# TH_Board.net
KiCad netlist of a schematic drawn in Altium Designer
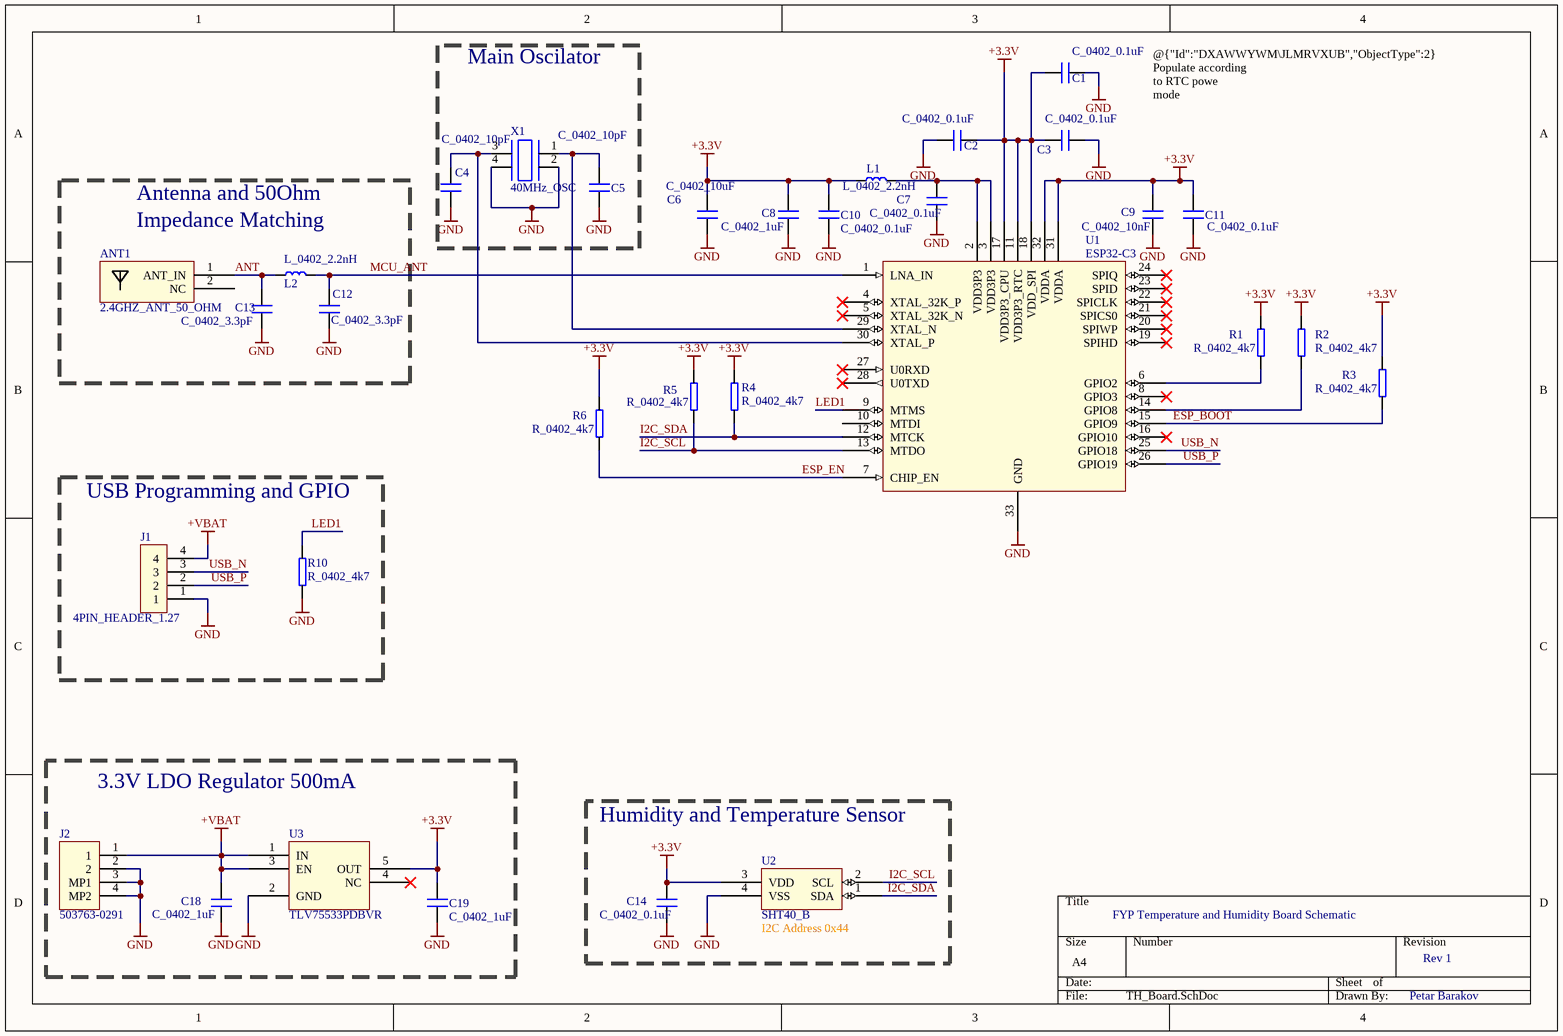
[diagram p0: TH_Board.SchDoc]

(export (version "E")
  (design (tool "Eeschema 10.0.6"))
  (components
    (comp (ref "ANT1")
      (value "2.4GHZ_ANT_50_OHM")
      (footprint "Chip2PinSM127P600-8N")
      (description "2.4GHz Chip Antenna 50 Ohm Impedance ANT2012LL00R2400A")
      (libsource (lib "Petar B") (part "2.4GHZ_ANT_50_OHM"))
    )
    (comp (ref "C1")
      (value "C_0402_0.1uF")
      (footprint "C_0402")
      (fields (field (name "JLC PART NUMBER") "C1525"))
      (libsource (lib "Petar B") (part "Cap_symbol"))
    )
    (comp (ref "C2")
      (value "C_0402_0.1uF")
      (footprint "C_0402")
      (fields (field (name "JLC PART NUMBER") "C1525"))
      (libsource (lib "Petar B") (part "Cap_symbol"))
    )
    (comp (ref "C3")
      (value "C_0402_0.1uF")
      (footprint "C_0402")
      (fields (field (name "JLC PART NUMBER") "C1525"))
      (libsource (lib "Petar B") (part "Cap_symbol"))
    )
    (comp (ref "C4")
      (value "C_0402_10pF")
      (footprint "C_0402")
      (fields (field (name "JLC PART NUMBER") "C32949"))
      (libsource (lib "Petar B") (part "Cap_symbol"))
    )
    (comp (ref "C5")
      (value "C_0402_10pF")
      (footprint "C_0402")
      (fields (field (name "JLC PART NUMBER") "C32949"))
      (libsource (lib "Petar B") (part "Cap_symbol"))
    )
    (comp (ref "C6")
      (value "C_0402_10uF")
      (footprint "C_0402")
      (fields (field (name "JLC PART NUMBER") "C15525"))
      (libsource (lib "Petar B") (part "Cap_symbol"))
    )
    (comp (ref "C7")
      (value "C_0402_0.1uF")
      (footprint "C_0402")
      (fields (field (name "JLC PART NUMBER") "C1525"))
      (libsource (lib "Petar B") (part "Cap_symbol"))
    )
    (comp (ref "C8")
      (value "C_0402_1uF")
      (footprint "C_0402")
      (fields (field (name "JLC PART NUMBER") "C52923"))
      (libsource (lib "Petar B") (part "Cap_symbol"))
    )
    (comp (ref "C9")
      (value "C_0402_10nF")
      (footprint "C_0402")
      (fields (field (name "JLC PART NUMBER") "C15195"))
      (libsource (lib "Petar B") (part "Cap_symbol"))
    )
    (comp (ref "C10")
      (value "C_0402_0.1uF")
      (footprint "C_0402")
      (fields (field (name "JLC PART NUMBER") "C1525"))
      (libsource (lib "Petar B") (part "Cap_symbol"))
    )
    (comp (ref "C11")
      (value "C_0402_0.1uF")
      (footprint "C_0402")
      (fields (field (name "JLC PART NUMBER") "C1525"))
      (libsource (lib "Petar B") (part "Cap_symbol"))
    )
    (comp (ref "C12")
      (value "C_0402_3.3pF")
      (footprint "C_0402")
      (fields (field (name "JLC PART NUMBER") "C326841"))
      (libsource (lib "Petar B") (part "Cap_symbol"))
    )
    (comp (ref "C13")
      (value "C_0402_3.3pF")
      (footprint "C_0402")
      (fields (field (name "JLC PART NUMBER") "C326841"))
      (libsource (lib "Petar B") (part "Cap_symbol"))
    )
    (comp (ref "C14")
      (value "C_0402_0.1uF")
      (footprint "C_0402")
      (fields (field (name "JLC PART NUMBER") "C1525"))
      (libsource (lib "Petar B") (part "Cap_symbol"))
    )
    (comp (ref "C18")
      (value "C_0402_1uF")
      (footprint "C_0402")
      (fields (field (name "JLC PART NUMBER") "C52923"))
      (libsource (lib "Petar B") (part "Cap_symbol"))
    )
    (comp (ref "C19")
      (value "C_0402_1uF")
      (footprint "C_0402")
      (fields (field (name "JLC PART NUMBER") "C52923"))
      (libsource (lib "Petar B") (part "Cap_symbol"))
    )
    (comp (ref "J1")
      (value "4PIN_HEADER_1.27")
      (footprint "4PIN_HEADER_1.27-Footprint-1")
      (libsource (lib "Petar B") (part "4PIN_HEADER_1.27-Symbol-1"))
    )
    (comp (ref "J2")
      (value "503763-0291")
      (footprint "Molex 503763-0291")
      (description "Molex 503763-0291")
      (libsource (lib "Petar B") (part "503763-0291"))
    )
    (comp (ref "L1")
      (value "L_0402_2.2nH")
      (footprint "L_0402")
      (fields (field (name "JLC PART NUMBER") "C92035"))
      (libsource (lib "Petar B") (part "Ind_Symbol"))
    )
    (comp (ref "L2")
      (value "L_0402_2.2nH")
      (footprint "L_0402")
      (fields (field (name "JLC PART NUMBER") "C92035"))
      (libsource (lib "Petar B") (part "Ind_Symbol"))
    )
    (comp (ref "R1")
      (value "R_0402_4k7")
      (footprint "R_0402")
      (fields (field (name "JLC PART NUMBER") "C25900"))
      (libsource (lib "Petar B") (part "R_symbol"))
    )
    (comp (ref "R2")
      (value "R_0402_4k7")
      (footprint "R_0402")
      (fields (field (name "JLC PART NUMBER") "C25900"))
      (libsource (lib "Petar B") (part "R_symbol"))
    )
    (comp (ref "R3")
      (value "R_0402_4k7")
      (footprint "R_0402")
      (fields (field (name "JLC PART NUMBER") "C25900"))
      (libsource (lib "Petar B") (part "R_symbol"))
    )
    (comp (ref "R4")
      (value "R_0402_4k7")
      (footprint "R_0402")
      (fields (field (name "JLC PART NUMBER") "C25900"))
      (libsource (lib "Petar B") (part "R_symbol"))
    )
    (comp (ref "R5")
      (value "R_0402_4k7")
      (footprint "R_0402")
      (fields (field (name "JLC PART NUMBER") "C25900"))
      (libsource (lib "Petar B") (part "R_symbol"))
    )
    (comp (ref "R6")
      (value "R_0402_4k7")
      (footprint "R_0402")
      (fields (field (name "JLC PART NUMBER") "C25900"))
      (libsource (lib "Petar B") (part "R_symbol"))
    )
    (comp (ref "R10")
      (value "R_0402_4k7")
      (footprint "R_0402")
      (fields (field (name "JLC PART NUMBER") "C25900"))
      (libsource (lib "Petar B") (part "R_symbol"))
    )
    (comp (ref "U1")
      (value "ESP32-C3")
      (footprint "QFN127P600-8N")
      (description "33 pin ESP32_C3 Microcontroller")
      (fields (field (name "JLC PART NUMBER") "C2858491"))
      (libsource (lib "Petar B") (part "ESP32-C3_symbol"))
    )
    (comp (ref "U2")
      (value "SHT40_B")
      (footprint "SHT40_B-Footprint-1")
      (fields (field (name "JLC PART NUMBER") "C3664342"))
      (libsource (lib "Petar B") (part "SHT40"))
    )
    (comp (ref "U3")
      (value "TLV75533PDBVR")
      (footprint "SOT95P280X145-5N")
      (fields (field (name "JLC PART NUMBER") "C404027"))
      (libsource (lib "Petar B") (part "TLV75533PDBVR-Symbol"))
    )
    (comp (ref "X1")
      (value "40MHz_OSC")
      (footprint "40MHz_OSC-Footprint-1")
      (description "40 MHZ Oscillator, 10pF load capacitance")
      (fields (field (name "JLC PART NUMBER") "C426988"))
      (libsource (lib "Petar B") (part "OSC_SYMB"))
    )
  )
  (nets
    (net (code "1") (name "+3.3V") (class "Default")
      (node (ref "C1") (pin "1") (pinfunction "1_1") (pintype "passive"))
      (node (ref "C10") (pin "1") (pinfunction "1_1") (pintype "passive"))
      (node (ref "C11") (pin "2") (pinfunction "2_2") (pintype "passive"))
      (node (ref "C14") (pin "1") (pinfunction "1_1") (pintype "passive"))
      (node (ref "C19") (pin "2") (pinfunction "2_2") (pintype "passive"))
      (node (ref "C2") (pin "2") (pinfunction "2_2") (pintype "passive"))
      (node (ref "C3") (pin "1") (pinfunction "1_1") (pintype "passive"))
      (node (ref "C6") (pin "2") (pinfunction "2_2") (pintype "passive"))
      (node (ref "C8") (pin "2") (pinfunction "2_2") (pintype "passive"))
      (node (ref "C9") (pin "2") (pinfunction "2_2") (pintype "passive"))
      (node (ref "L1") (pin "1") (pinfunction "1_1") (pintype "passive"))
      (node (ref "R1") (pin "1") (pinfunction "1_1") (pintype "passive"))
      (node (ref "R2") (pin "1") (pinfunction "1_1") (pintype "passive"))
      (node (ref "R3") (pin "1") (pinfunction "1_1") (pintype "passive"))
      (node (ref "R4") (pin "1") (pinfunction "1_1") (pintype "passive"))
      (node (ref "R5") (pin "1") (pinfunction "1_1") (pintype "passive"))
      (node (ref "R6") (pin "1") (pinfunction "1_1") (pintype "passive"))
      (node (ref "U1") (pin "11") (pinfunction "VDD3P3_RTC_11") (pintype "power_in"))
      (node (ref "U1") (pin "17") (pinfunction "VDD3P3_CPU_17") (pintype "power_in"))
      (node (ref "U1") (pin "18") (pinfunction "VDD_SPI_18") (pintype "power_in"))
      (node (ref "U1") (pin "31") (pinfunction "VDDA_31") (pintype "power_in"))
      (node (ref "U1") (pin "32") (pinfunction "VDDA_32") (pintype "power_in"))
      (node (ref "U2") (pin "3") (pinfunction "VDD_3") (pintype "power_in"))
      (node (ref "U3") (pin "5") (pinfunction "OUT_5") (pintype "passive"))
    )
    (net (code "2") (name "+VBAT") (class "Default")
      (node (ref "C18") (pin "2") (pinfunction "2_2") (pintype "passive"))
      (node (ref "J1") (pin "4") (pinfunction "4_4") (pintype "passive"))
      (node (ref "J2") (pin "1") (pinfunction "1_1") (pintype "passive"))
      (node (ref "U3") (pin "1") (pinfunction "IN_1") (pintype "passive"))
      (node (ref "U3") (pin "3") (pinfunction "EN_3") (pintype "passive"))
    )
    (net (code "3") (name "/ANT") (class "Default")
      (node (ref "ANT1") (pin "1") (pinfunction "ANT_IN_1") (pintype "passive"))
      (node (ref "C13") (pin "2") (pinfunction "2_2") (pintype "passive"))
      (node (ref "L2") (pin "1") (pinfunction "1_1") (pintype "passive"))
    )
    (net (code "4") (name "/ESP_BOOT") (class "Default")
      (node (ref "R3") (pin "2") (pinfunction "2_2") (pintype "passive"))
      (node (ref "U1") (pin "15") (pinfunction "GPIO9_15") (pintype "bidirectional"))
    )
    (net (code "5") (name "/ESP_EN") (class "Default")
      (node (ref "R6") (pin "2") (pinfunction "2_2") (pintype "passive"))
      (node (ref "U1") (pin "7") (pinfunction "CHIP_EN_7") (pintype "input"))
    )
    (net (code "6") (name "/I2C_SCL") (class "Default")
      (node (ref "R5") (pin "2") (pinfunction "2_2") (pintype "passive"))
      (node (ref "U1") (pin "13") (pinfunction "MTDO_13") (pintype "bidirectional"))
      (node (ref "U2") (pin "2") (pinfunction "SCL_2") (pintype "bidirectional"))
    )
    (net (code "7") (name "/I2C_SDA") (class "Default")
      (node (ref "R4") (pin "2") (pinfunction "2_2") (pintype "passive"))
      (node (ref "U1") (pin "12") (pinfunction "MTCK_12") (pintype "bidirectional"))
      (node (ref "U2") (pin "1") (pinfunction "SDA_1") (pintype "bidirectional"))
    )
    (net (code "8") (name "/LED1") (class "Default")
      (node (ref "R10") (pin "1") (pinfunction "1_1") (pintype "passive"))
      (node (ref "U1") (pin "9") (pinfunction "MTMS_9") (pintype "bidirectional"))
    )
    (net (code "9") (name "/MCU_ANT") (class "Default")
      (node (ref "C12") (pin "2") (pinfunction "2_2") (pintype "passive"))
      (node (ref "L2") (pin "2") (pinfunction "2_2") (pintype "passive"))
      (node (ref "U1") (pin "1") (pinfunction "LNA_IN_1") (pintype "input"))
    )
    (net (code "10") (name "/USB_N") (class "Default")
      (node (ref "J1") (pin "3") (pinfunction "3_3") (pintype "passive"))
      (node (ref "U1") (pin "25") (pinfunction "GPIO18_25") (pintype "bidirectional"))
    )
    (net (code "11") (name "/USB_P") (class "Default")
      (node (ref "J1") (pin "2") (pinfunction "2_2") (pintype "passive"))
      (node (ref "U1") (pin "26") (pinfunction "GPIO19_26") (pintype "bidirectional"))
    )
    (net (code "12") (name "GND") (class "Default")
      (node (ref "C1") (pin "2") (pinfunction "2_2") (pintype "passive"))
      (node (ref "C10") (pin "2") (pinfunction "2_2") (pintype "passive"))
      (node (ref "C11") (pin "1") (pinfunction "1_1") (pintype "passive"))
      (node (ref "C12") (pin "1") (pinfunction "1_1") (pintype "passive"))
      (node (ref "C13") (pin "1") (pinfunction "1_1") (pintype "passive"))
      (node (ref "C14") (pin "2") (pinfunction "2_2") (pintype "passive"))
      (node (ref "C18") (pin "1") (pinfunction "1_1") (pintype "passive"))
      (node (ref "C19") (pin "1") (pinfunction "1_1") (pintype "passive"))
      (node (ref "C2") (pin "1") (pinfunction "1_1") (pintype "passive"))
      (node (ref "C3") (pin "2") (pinfunction "2_2") (pintype "passive"))
      (node (ref "C4") (pin "1") (pinfunction "1_1") (pintype "passive"))
      (node (ref "C5") (pin "1") (pinfunction "1_1") (pintype "passive"))
      (node (ref "C6") (pin "1") (pinfunction "1_1") (pintype "passive"))
      (node (ref "C7") (pin "2") (pinfunction "2_2") (pintype "passive"))
      (node (ref "C8") (pin "1") (pinfunction "1_1") (pintype "passive"))
      (node (ref "C9") (pin "1") (pinfunction "1_1") (pintype "passive"))
      (node (ref "J1") (pin "1") (pinfunction "1_1") (pintype "passive"))
      (node (ref "J2") (pin "2") (pinfunction "2_2") (pintype "passive"))
      (node (ref "J2") (pin "3") (pinfunction "MP1_3") (pintype "passive"))
      (node (ref "J2") (pin "4") (pinfunction "MP2_4") (pintype "passive"))
      (node (ref "R10") (pin "2") (pinfunction "2_2") (pintype "passive"))
      (node (ref "U1") (pin "33") (pinfunction "GND_33") (pintype "power_in"))
      (node (ref "U2") (pin "4") (pinfunction "VSS_4") (pintype "power_in"))
      (node (ref "U3") (pin "2") (pinfunction "GND_2") (pintype "passive"))
      (node (ref "X1") (pin "2") (pinfunction "2_2") (pintype "passive"))
      (node (ref "X1") (pin "4") (pinfunction "4_4") (pintype "passive"))
    )
    (net (code "13") (name "Net-(C7-Pad1)") (class "Default")
      (node (ref "C7") (pin "1") (pinfunction "1_1") (pintype "passive"))
      (node (ref "L1") (pin "2") (pinfunction "2_2") (pintype "passive"))
      (node (ref "U1") (pin "2") (pinfunction "VDD3P3_2") (pintype "power_in"))
      (node (ref "U1") (pin "3") (pinfunction "VDD3P3_3") (pintype "power_in"))
    )
    (net (code "14") (name "Net-(U1-GPIO2)") (class "Default")
      (node (ref "R1") (pin "2") (pinfunction "2_2") (pintype "passive"))
      (node (ref "U1") (pin "6") (pinfunction "GPIO2_6") (pintype "bidirectional"))
    )
    (net (code "15") (name "Net-(U1-GPIO8)") (class "Default")
      (node (ref "R2") (pin "2") (pinfunction "2_2") (pintype "passive"))
      (node (ref "U1") (pin "14") (pinfunction "GPIO8_14") (pintype "bidirectional"))
    )
    (net (code "16") (name "Net-(U1-XTAL_N)") (class "Default")
      (node (ref "C5") (pin "2") (pinfunction "2_2") (pintype "passive"))
      (node (ref "U1") (pin "29") (pinfunction "XTAL_N_29") (pintype "bidirectional"))
      (node (ref "X1") (pin "1") (pinfunction "1_1") (pintype "passive"))
    )
    (net (code "17") (name "Net-(U1-XTAL_P)") (class "Default")
      (node (ref "C4") (pin "2") (pinfunction "2_2") (pintype "passive"))
      (node (ref "U1") (pin "30") (pinfunction "XTAL_P_30") (pintype "bidirectional"))
      (node (ref "X1") (pin "3") (pinfunction "3_3") (pintype "passive"))
    )
    (net (code "18") (name "unconnected-(ANT1-NC-Pad2)") (class "Default")
      (node (ref "ANT1") (pin "2") (pinfunction "NC_2") (pintype "passive"))
    )
    (net (code "19") (name "unconnected-(U1-GPIO3-Pad8)") (class "Default")
      (node (ref "U1") (pin "8") (pinfunction "GPIO3_8") (pintype "bidirectional+no_connect"))
    )
    (net (code "20") (name "unconnected-(U1-GPIO10-Pad16)") (class "Default")
      (node (ref "U1") (pin "16") (pinfunction "GPIO10_16") (pintype "bidirectional+no_connect"))
    )
    (net (code "21") (name "unconnected-(U1-MTDI-Pad10)") (class "Default")
      (node (ref "U1") (pin "10") (pinfunction "MTDI_10") (pintype "bidirectional"))
    )
    (net (code "22") (name "unconnected-(U1-SPICLK-Pad22)") (class "Default")
      (node (ref "U1") (pin "22") (pinfunction "SPICLK_22") (pintype "bidirectional+no_connect"))
    )
    (net (code "23") (name "unconnected-(U1-SPICS0-Pad21)") (class "Default")
      (node (ref "U1") (pin "21") (pinfunction "SPICS0_21") (pintype "bidirectional+no_connect"))
    )
    (net (code "24") (name "unconnected-(U1-SPID-Pad23)") (class "Default")
      (node (ref "U1") (pin "23") (pinfunction "SPID_23") (pintype "bidirectional+no_connect"))
    )
    (net (code "25") (name "unconnected-(U1-SPIHD-Pad19)") (class "Default")
      (node (ref "U1") (pin "19") (pinfunction "SPIHD_19") (pintype "bidirectional+no_connect"))
    )
    (net (code "26") (name "unconnected-(U1-SPIQ-Pad24)") (class "Default")
      (node (ref "U1") (pin "24") (pinfunction "SPIQ_24") (pintype "bidirectional+no_connect"))
    )
    (net (code "27") (name "unconnected-(U1-SPIWP-Pad20)") (class "Default")
      (node (ref "U1") (pin "20") (pinfunction "SPIWP_20") (pintype "bidirectional+no_connect"))
    )
    (net (code "28") (name "unconnected-(U1-U0RXD-Pad27)") (class "Default")
      (node (ref "U1") (pin "27") (pinfunction "U0RXD_27") (pintype "input+no_connect"))
    )
    (net (code "29") (name "unconnected-(U1-U0TXD-Pad28)") (class "Default")
      (node (ref "U1") (pin "28") (pinfunction "U0TXD_28") (pintype "output+no_connect"))
    )
    (net (code "30") (name "unconnected-(U1-XTAL_32K_N-Pad5)") (class "Default")
      (node (ref "U1") (pin "5") (pinfunction "XTAL_32K_N_5") (pintype "bidirectional+no_connect"))
    )
    (net (code "31") (name "unconnected-(U1-XTAL_32K_P-Pad4)") (class "Default")
      (node (ref "U1") (pin "4") (pinfunction "XTAL_32K_P_4") (pintype "bidirectional+no_connect"))
    )
    (net (code "32") (name "unconnected-(U3-NC-Pad4)") (class "Default")
      (node (ref "U3") (pin "4") (pinfunction "NC_4") (pintype "passive+no_connect"))
    )
  )
)
